# jtag-adapter-1-2.net
KiCad netlist of a schematic drawn in EAGLE
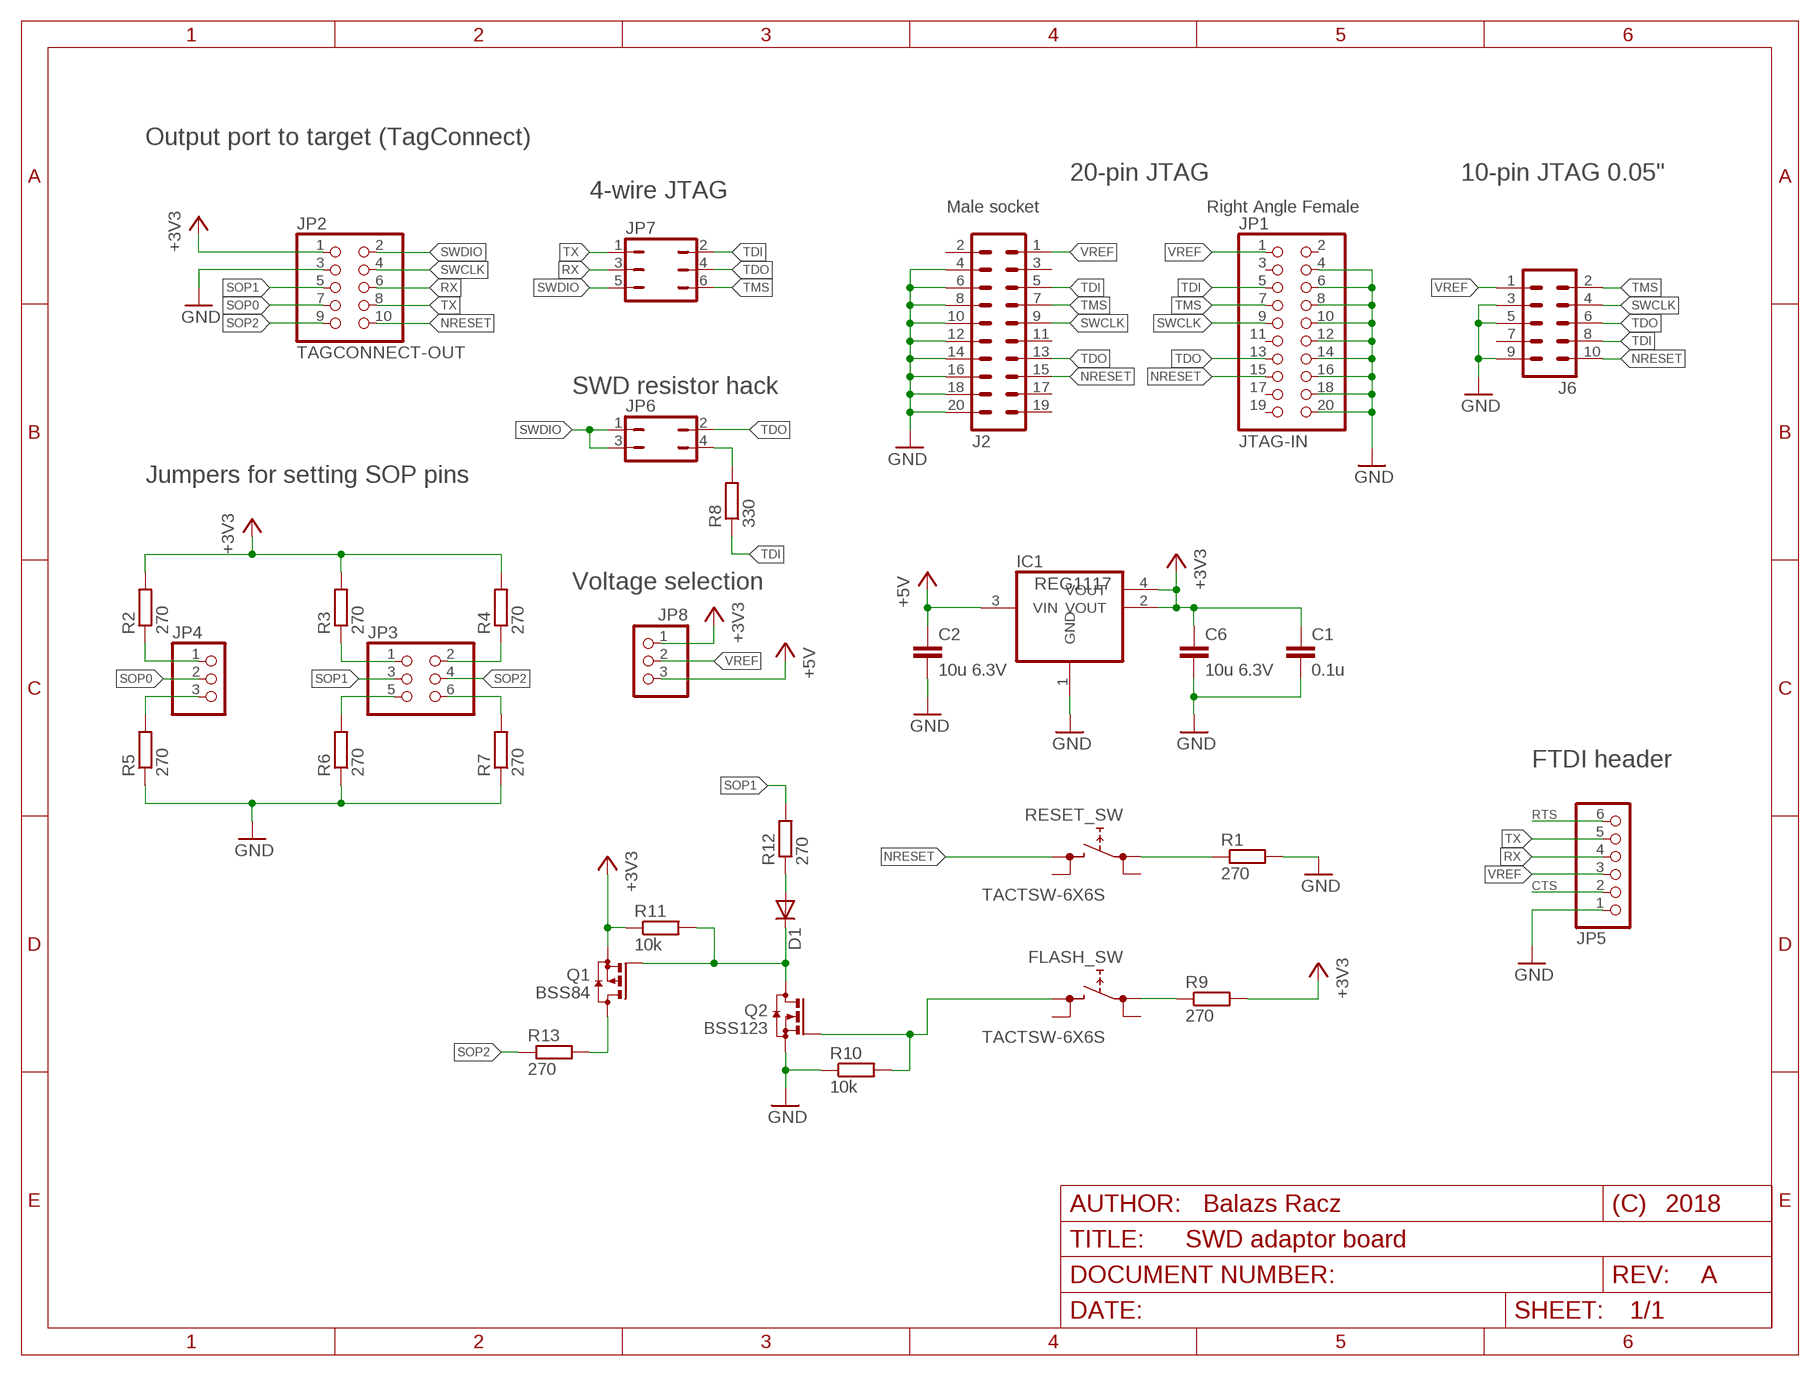
[diagram p0: schematic, sheet 1]

(export (version "E")
  (design (tool "Eeschema 10.0.6"))
  (components
    (comp (ref "C1")
      (value "0.1u")
      (footprint "eagle-import:C0603K")
      (libsource (lib "eagle-import") (part "C-EUC0603K"))
    )
    (comp (ref "C2")
      (value "10u 6.3V")
      (footprint "eagle-import:C0603K")
      (libsource (lib "eagle-import") (part "C-EUC0603K"))
    )
    (comp (ref "C6")
      (value "10u 6.3V")
      (footprint "eagle-import:C0603K")
      (libsource (lib "eagle-import") (part "C-EUC0603K"))
    )
    (comp (ref "D1")
      (value "DIODE-MINIMELF")
      (footprint "eagle-import:MINIMELF")
      (libsource (lib "eagle-import") (part "DIODE-MINIMELF"))
    )
    (comp (ref "FLASH_SW")
      (value "TACTSW-6X6S")
      (footprint "eagle-import:TACTSW-6X6")
      (libsource (lib "eagle-import") (part "TACTSW-6X6S"))
    )
    (comp (ref "IC1")
      (value "REG1117")
      (footprint "eagle-import:SOT223")
      (libsource (lib "eagle-import") (part "REG1117"))
    )
    (comp (ref "J2")
      (value "MA10-2S")
      (footprint "eagle-import:MA10-2-SHROUDED")
      (libsource (lib "eagle-import") (part "MA10-2S"))
    )
    (comp (ref "J6")
      (value "MA05-2_0.05X0.05")
      (footprint "eagle-import:MA05-2_0.05_X_0.05")
      (libsource (lib "eagle-import") (part "MA05-2_0.05X0.05"))
    )
    (comp (ref "JP1")
      (value "JTAG-IN")
      (footprint "eagle-import:2X10_90")
      (libsource (lib "eagle-import") (part "PINHD-2X10/90"))
    )
    (comp (ref "JP2")
      (value "TAGCONNECT-OUT")
      (footprint "eagle-import:CON10M")
      (libsource (lib "eagle-import") (part "PINHD-2X5CN"))
    )
    (comp (ref "JP3")
      (value "PINHD-2X3")
      (footprint "eagle-import:2X03")
      (libsource (lib "eagle-import") (part "PINHD-2X3"))
    )
    (comp (ref "JP4")
      (value "PINHD-1X3")
      (footprint "eagle-import:1X03")
      (libsource (lib "eagle-import") (part "PINHD-1X3"))
    )
    (comp (ref "JP5")
      (value "PINHD-1X6")
      (footprint "eagle-import:1X06")
      (libsource (lib "eagle-import") (part "PINHD-1X6"))
    )
    (comp (ref "JP6")
      (value "JP2Q")
      (footprint "eagle-import:JP2Q")
      (libsource (lib "eagle-import") (part "JP2Q"))
    )
    (comp (ref "JP7")
      (value "JP3Q")
      (footprint "eagle-import:JP3Q")
      (libsource (lib "eagle-import") (part "JP3Q"))
    )
    (comp (ref "JP8")
      (value "PINHD-1X3")
      (footprint "eagle-import:1X03")
      (libsource (lib "eagle-import") (part "PINHD-1X3"))
    )
    (comp (ref "Q1")
      (value "BSS84")
      (footprint "eagle-import:SOT23")
      (libsource (lib "eagle-import") (part "BSS84"))
    )
    (comp (ref "Q2")
      (value "BSS123")
      (footprint "eagle-import:SOT23")
      (libsource (lib "eagle-import") (part "BSS123"))
    )
    (comp (ref "R1")
      (value "270")
      (footprint "eagle-import:R0805")
      (libsource (lib "eagle-import") (part "R-EU_R0805"))
    )
    (comp (ref "R2")
      (value "270")
      (footprint "eagle-import:R0805")
      (libsource (lib "eagle-import") (part "R-EU_R0805"))
    )
    (comp (ref "R3")
      (value "270")
      (footprint "eagle-import:R0805")
      (libsource (lib "eagle-import") (part "R-EU_R0805"))
    )
    (comp (ref "R4")
      (value "270")
      (footprint "eagle-import:R0805")
      (libsource (lib "eagle-import") (part "R-EU_R0805"))
    )
    (comp (ref "R5")
      (value "270")
      (footprint "eagle-import:R0805")
      (libsource (lib "eagle-import") (part "R-EU_R0805"))
    )
    (comp (ref "R6")
      (value "270")
      (footprint "eagle-import:R0805")
      (libsource (lib "eagle-import") (part "R-EU_R0805"))
    )
    (comp (ref "R7")
      (value "270")
      (footprint "eagle-import:R0805")
      (libsource (lib "eagle-import") (part "R-EU_R0805"))
    )
    (comp (ref "R8")
      (value "330")
      (footprint "eagle-import:R0805")
      (libsource (lib "eagle-import") (part "R-EU_R0805"))
    )
    (comp (ref "R9")
      (value "270")
      (footprint "eagle-import:R0805")
      (libsource (lib "eagle-import") (part "R-EU_R0805"))
    )
    (comp (ref "R10")
      (value "10k")
      (footprint "eagle-import:R0805")
      (libsource (lib "eagle-import") (part "R-EU_R0805"))
    )
    (comp (ref "R11")
      (value "10k")
      (footprint "eagle-import:R0805")
      (libsource (lib "eagle-import") (part "R-EU_R0805"))
    )
    (comp (ref "R12")
      (value "270")
      (footprint "eagle-import:R0805")
      (libsource (lib "eagle-import") (part "R-EU_R0805"))
    )
    (comp (ref "R13")
      (value "270")
      (footprint "eagle-import:R0805")
      (libsource (lib "eagle-import") (part "R-EU_R0805"))
    )
    (comp (ref "RESET_SW")
      (value "TACTSW-6X6S")
      (footprint "eagle-import:TACTSW-6X6")
      (libsource (lib "eagle-import") (part "TACTSW-6X6S"))
    )
  )
  (nets
    (net (code "1") (name "+3V3") (class "Default")
      (node (ref "C1") (pin "1") (pinfunction "1_1") (pintype "passive"))
      (node (ref "C6") (pin "1") (pinfunction "1_1") (pintype "passive"))
      (node (ref "IC1") (pin "2") (pinfunction "VOUT_2") (pintype "output"))
      (node (ref "IC1") (pin "4") (pinfunction "VOUT_4") (pintype "output"))
      (node (ref "JP2") (pin "1") (pinfunction "1_1") (pintype "passive"))
      (node (ref "JP8") (pin "1") (pinfunction "1_1") (pintype "passive"))
      (node (ref "Q1") (pin "2") (pinfunction "S_2") (pintype "passive"))
      (node (ref "R11") (pin "1") (pinfunction "1_1") (pintype "passive"))
      (node (ref "R2") (pin "2") (pinfunction "2_2") (pintype "passive"))
      (node (ref "R3") (pin "2") (pinfunction "2_2") (pintype "passive"))
      (node (ref "R4") (pin "2") (pinfunction "2_2") (pintype "passive"))
      (node (ref "R9") (pin "2") (pinfunction "2_2") (pintype "passive"))
    )
    (net (code "2") (name "+5V") (class "Default")
      (node (ref "C2") (pin "1") (pinfunction "1_1") (pintype "passive"))
      (node (ref "IC1") (pin "3") (pinfunction "VIN_3") (pintype "input"))
      (node (ref "JP8") (pin "3") (pinfunction "3_3") (pintype "passive"))
    )
    (net (code "3") (name "/CTS") (class "Default")
      (node (ref "JP5") (pin "2") (pinfunction "2_2") (pintype "passive"))
    )
    (net (code "4") (name "/RTS") (class "Default")
      (node (ref "JP5") (pin "6") (pinfunction "6_6") (pintype "passive"))
    )
    (net (code "5") (name "GND") (class "Default")
      (node (ref "C1") (pin "2") (pinfunction "2_2") (pintype "passive"))
      (node (ref "C2") (pin "2") (pinfunction "2_2") (pintype "passive"))
      (node (ref "C6") (pin "2") (pinfunction "2_2") (pintype "passive"))
      (node (ref "IC1") (pin "1") (pinfunction "GND_1") (pintype "power_in"))
      (node (ref "J2") (pin "10") (pinfunction "10_10") (pintype "passive"))
      (node (ref "J2") (pin "12") (pinfunction "12_12") (pintype "passive"))
      (node (ref "J2") (pin "14") (pinfunction "14_14") (pintype "passive"))
      (node (ref "J2") (pin "16") (pinfunction "16_16") (pintype "passive"))
      (node (ref "J2") (pin "18") (pinfunction "18_18") (pintype "passive"))
      (node (ref "J2") (pin "20") (pinfunction "20_20") (pintype "passive"))
      (node (ref "J2") (pin "4") (pinfunction "4_4") (pintype "passive"))
      (node (ref "J2") (pin "6") (pinfunction "6_6") (pintype "passive"))
      (node (ref "J2") (pin "8") (pinfunction "8_8") (pintype "passive"))
      (node (ref "J6") (pin "3") (pinfunction "3_3") (pintype "passive"))
      (node (ref "J6") (pin "5") (pinfunction "5_5") (pintype "passive"))
      (node (ref "J6") (pin "9") (pinfunction "9_9") (pintype "passive"))
      (node (ref "JP1") (pin "10") (pinfunction "10_10") (pintype "passive"))
      (node (ref "JP1") (pin "12") (pinfunction "12_12") (pintype "passive"))
      (node (ref "JP1") (pin "14") (pinfunction "14_14") (pintype "passive"))
      (node (ref "JP1") (pin "16") (pinfunction "16_16") (pintype "passive"))
      (node (ref "JP1") (pin "18") (pinfunction "18_18") (pintype "passive"))
      (node (ref "JP1") (pin "20") (pinfunction "20_20") (pintype "passive"))
      (node (ref "JP1") (pin "4") (pinfunction "4_4") (pintype "passive"))
      (node (ref "JP1") (pin "6") (pinfunction "6_6") (pintype "passive"))
      (node (ref "JP1") (pin "8") (pinfunction "8_8") (pintype "passive"))
      (node (ref "JP2") (pin "3") (pinfunction "3_3") (pintype "passive"))
      (node (ref "JP5") (pin "1") (pinfunction "1_1") (pintype "passive"))
      (node (ref "Q2") (pin "2") (pinfunction "S_2") (pintype "passive"))
      (node (ref "R1") (pin "2") (pinfunction "2_2") (pintype "passive"))
      (node (ref "R10") (pin "1") (pinfunction "1_1") (pintype "passive"))
      (node (ref "R5") (pin "1") (pinfunction "1_1") (pintype "passive"))
      (node (ref "R6") (pin "1") (pinfunction "1_1") (pintype "passive"))
      (node (ref "R7") (pin "1") (pinfunction "1_1") (pintype "passive"))
    )
    (net (code "6") (name "NRESET") (class "Default")
      (node (ref "J2") (pin "15") (pinfunction "15_15") (pintype "passive"))
      (node (ref "J6") (pin "10") (pinfunction "10_10") (pintype "passive"))
      (node (ref "JP1") (pin "15") (pinfunction "15_15") (pintype "passive"))
      (node (ref "JP2") (pin "10") (pinfunction "10_10") (pintype "passive"))
      (node (ref "RESET_SW") (pin "3") (pinfunction "2.1_3") (pintype "passive"))
    )
    (net (code "7") (name "Net-(D1-PadA)") (class "Default")
      (node (ref "D1") (pin "A") (pinfunction "A_A") (pintype "passive"))
      (node (ref "R12") (pin "1") (pinfunction "1_1") (pintype "passive"))
    )
    (net (code "8") (name "Net-(FLASH_SW-1.1)") (class "Default")
      (node (ref "FLASH_SW") (pin "1") (pinfunction "1.1_1") (pintype "passive"))
      (node (ref "R9") (pin "1") (pinfunction "1_1") (pintype "passive"))
    )
    (net (code "9") (name "Net-(FLASH_SW-2.1)") (class "Default")
      (node (ref "FLASH_SW") (pin "3") (pinfunction "2.1_3") (pintype "passive"))
      (node (ref "Q2") (pin "1") (pinfunction "G_1") (pintype "passive"))
      (node (ref "R10") (pin "2") (pinfunction "2_2") (pintype "passive"))
    )
    (net (code "10") (name "Net-(JP3-Pad1)") (class "Default")
      (node (ref "JP3") (pin "1") (pinfunction "1_1") (pintype "passive"))
      (node (ref "R3") (pin "1") (pinfunction "1_1") (pintype "passive"))
    )
    (net (code "11") (name "Net-(JP3-Pad2)") (class "Default")
      (node (ref "JP3") (pin "2") (pinfunction "2_2") (pintype "passive"))
      (node (ref "R4") (pin "1") (pinfunction "1_1") (pintype "passive"))
    )
    (net (code "12") (name "Net-(JP3-Pad5)") (class "Default")
      (node (ref "JP3") (pin "5") (pinfunction "5_5") (pintype "passive"))
      (node (ref "R6") (pin "2") (pinfunction "2_2") (pintype "passive"))
    )
    (net (code "13") (name "Net-(JP3-Pad6)") (class "Default")
      (node (ref "JP3") (pin "6") (pinfunction "6_6") (pintype "passive"))
      (node (ref "R7") (pin "2") (pinfunction "2_2") (pintype "passive"))
    )
    (net (code "14") (name "Net-(JP4-Pad1)") (class "Default")
      (node (ref "JP4") (pin "1") (pinfunction "1_1") (pintype "passive"))
      (node (ref "R2") (pin "1") (pinfunction "1_1") (pintype "passive"))
    )
    (net (code "15") (name "Net-(JP4-Pad3)") (class "Default")
      (node (ref "JP4") (pin "3") (pinfunction "3_3") (pintype "passive"))
      (node (ref "R5") (pin "2") (pinfunction "2_2") (pintype "passive"))
    )
    (net (code "16") (name "Net-(JP6-Pad4)") (class "Default")
      (node (ref "JP6") (pin "4") (pinfunction "4_4") (pintype "passive"))
      (node (ref "R8") (pin "2") (pinfunction "2_2") (pintype "passive"))
    )
    (net (code "17") (name "Net-(Q1-D)") (class "Default")
      (node (ref "Q1") (pin "3") (pinfunction "D_3") (pintype "passive"))
      (node (ref "R13") (pin "2") (pinfunction "2_2") (pintype "passive"))
    )
    (net (code "18") (name "Net-(Q1-G)") (class "Default")
      (node (ref "D1") (pin "C") (pinfunction "C_C") (pintype "passive"))
      (node (ref "Q1") (pin "1") (pinfunction "G_1") (pintype "passive"))
      (node (ref "Q2") (pin "3") (pinfunction "D_3") (pintype "passive"))
      (node (ref "R11") (pin "2") (pinfunction "2_2") (pintype "passive"))
    )
    (net (code "19") (name "Net-(RESET_SW-1.1)") (class "Default")
      (node (ref "R1") (pin "1") (pinfunction "1_1") (pintype "passive"))
      (node (ref "RESET_SW") (pin "1") (pinfunction "1.1_1") (pintype "passive"))
    )
    (net (code "20") (name "RX") (class "Default")
      (node (ref "JP2") (pin "6") (pinfunction "6_6") (pintype "passive"))
      (node (ref "JP5") (pin "4") (pinfunction "4_4") (pintype "passive"))
      (node (ref "JP7") (pin "3") (pinfunction "3_3") (pintype "passive"))
    )
    (net (code "21") (name "SOP0") (class "Default")
      (node (ref "JP2") (pin "7") (pinfunction "7_7") (pintype "passive"))
      (node (ref "JP4") (pin "2") (pinfunction "2_2") (pintype "passive"))
    )
    (net (code "22") (name "SOP1") (class "Default")
      (node (ref "JP2") (pin "5") (pinfunction "5_5") (pintype "passive"))
      (node (ref "JP3") (pin "3") (pinfunction "3_3") (pintype "passive"))
      (node (ref "R12") (pin "2") (pinfunction "2_2") (pintype "passive"))
    )
    (net (code "23") (name "SOP2") (class "Default")
      (node (ref "JP2") (pin "9") (pinfunction "9_9") (pintype "passive"))
      (node (ref "JP3") (pin "4") (pinfunction "4_4") (pintype "passive"))
      (node (ref "R13") (pin "1") (pinfunction "1_1") (pintype "passive"))
    )
    (net (code "24") (name "SWCLK") (class "Default")
      (node (ref "J2") (pin "9") (pinfunction "9_9") (pintype "passive"))
      (node (ref "J6") (pin "4") (pinfunction "4_4") (pintype "passive"))
      (node (ref "JP1") (pin "9") (pinfunction "9_9") (pintype "passive"))
      (node (ref "JP2") (pin "4") (pinfunction "4_4") (pintype "passive"))
    )
    (net (code "25") (name "SWDIO") (class "Default")
      (node (ref "JP2") (pin "2") (pinfunction "2_2") (pintype "passive"))
      (node (ref "JP6") (pin "1") (pinfunction "1_1") (pintype "passive"))
      (node (ref "JP6") (pin "3") (pinfunction "3_3") (pintype "passive"))
      (node (ref "JP7") (pin "5") (pinfunction "5_5") (pintype "passive"))
    )
    (net (code "26") (name "TDI") (class "Default")
      (node (ref "J2") (pin "5") (pinfunction "5_5") (pintype "passive"))
      (node (ref "J6") (pin "8") (pinfunction "8_8") (pintype "passive"))
      (node (ref "JP1") (pin "5") (pinfunction "5_5") (pintype "passive"))
      (node (ref "JP7") (pin "2") (pinfunction "2_2") (pintype "passive"))
      (node (ref "R8") (pin "1") (pinfunction "1_1") (pintype "passive"))
    )
    (net (code "27") (name "TDO") (class "Default")
      (node (ref "J2") (pin "13") (pinfunction "13_13") (pintype "passive"))
      (node (ref "J6") (pin "6") (pinfunction "6_6") (pintype "passive"))
      (node (ref "JP1") (pin "13") (pinfunction "13_13") (pintype "passive"))
      (node (ref "JP6") (pin "2") (pinfunction "2_2") (pintype "passive"))
      (node (ref "JP7") (pin "4") (pinfunction "4_4") (pintype "passive"))
    )
    (net (code "28") (name "TMS") (class "Default")
      (node (ref "J2") (pin "7") (pinfunction "7_7") (pintype "passive"))
      (node (ref "J6") (pin "2") (pinfunction "2_2") (pintype "passive"))
      (node (ref "JP1") (pin "7") (pinfunction "7_7") (pintype "passive"))
      (node (ref "JP7") (pin "6") (pinfunction "6_6") (pintype "passive"))
    )
    (net (code "29") (name "TX") (class "Default")
      (node (ref "JP2") (pin "8") (pinfunction "8_8") (pintype "passive"))
      (node (ref "JP5") (pin "5") (pinfunction "5_5") (pintype "passive"))
      (node (ref "JP7") (pin "1") (pinfunction "1_1") (pintype "passive"))
    )
    (net (code "30") (name "VREF") (class "Default")
      (node (ref "J2") (pin "1") (pinfunction "1_1") (pintype "passive"))
      (node (ref "J6") (pin "1") (pinfunction "1_1") (pintype "passive"))
      (node (ref "JP1") (pin "1") (pinfunction "1_1") (pintype "passive"))
      (node (ref "JP5") (pin "3") (pinfunction "3_3") (pintype "passive"))
      (node (ref "JP8") (pin "2") (pinfunction "2_2") (pintype "passive"))
    )
    (net (code "31") (name "unconnected-(FLASH_SW-1.2-Pad2)") (class "Default")
      (node (ref "FLASH_SW") (pin "2") (pinfunction "1.2_2") (pintype "passive"))
    )
    (net (code "32") (name "unconnected-(FLASH_SW-2.2-Pad4)") (class "Default")
      (node (ref "FLASH_SW") (pin "4") (pinfunction "2.2_4") (pintype "passive"))
    )
    (net (code "33") (name "unconnected-(J2-Pad2)") (class "Default")
      (node (ref "J2") (pin "2") (pinfunction "2_2") (pintype "passive"))
    )
    (net (code "34") (name "unconnected-(J2-Pad3)") (class "Default")
      (node (ref "J2") (pin "3") (pinfunction "3_3") (pintype "passive"))
    )
    (net (code "35") (name "unconnected-(J2-Pad11)") (class "Default")
      (node (ref "J2") (pin "11") (pinfunction "11_11") (pintype "passive"))
    )
    (net (code "36") (name "unconnected-(J2-Pad17)") (class "Default")
      (node (ref "J2") (pin "17") (pinfunction "17_17") (pintype "passive"))
    )
    (net (code "37") (name "unconnected-(J2-Pad19)") (class "Default")
      (node (ref "J2") (pin "19") (pinfunction "19_19") (pintype "passive"))
    )
    (net (code "38") (name "unconnected-(J6-Pad7)") (class "Default")
      (node (ref "J6") (pin "7") (pinfunction "7_7") (pintype "passive"))
    )
    (net (code "39") (name "unconnected-(JP1-Pad2)") (class "Default")
      (node (ref "JP1") (pin "2") (pinfunction "2_2") (pintype "passive"))
    )
    (net (code "40") (name "unconnected-(JP1-Pad3)") (class "Default")
      (node (ref "JP1") (pin "3") (pinfunction "3_3") (pintype "passive"))
    )
    (net (code "41") (name "unconnected-(JP1-Pad11)") (class "Default")
      (node (ref "JP1") (pin "11") (pinfunction "11_11") (pintype "passive"))
    )
    (net (code "42") (name "unconnected-(JP1-Pad17)") (class "Default")
      (node (ref "JP1") (pin "17") (pinfunction "17_17") (pintype "passive"))
    )
    (net (code "43") (name "unconnected-(JP1-Pad19)") (class "Default")
      (node (ref "JP1") (pin "19") (pinfunction "19_19") (pintype "passive"))
    )
    (net (code "44") (name "unconnected-(RESET_SW-1.2-Pad2)") (class "Default")
      (node (ref "RESET_SW") (pin "2") (pinfunction "1.2_2") (pintype "passive"))
    )
    (net (code "45") (name "unconnected-(RESET_SW-2.2-Pad4)") (class "Default")
      (node (ref "RESET_SW") (pin "4") (pinfunction "2.2_4") (pintype "passive"))
    )
  )
)
